# fz10_pow.net
KiCad netlist of a schematic drawn in EAGLE
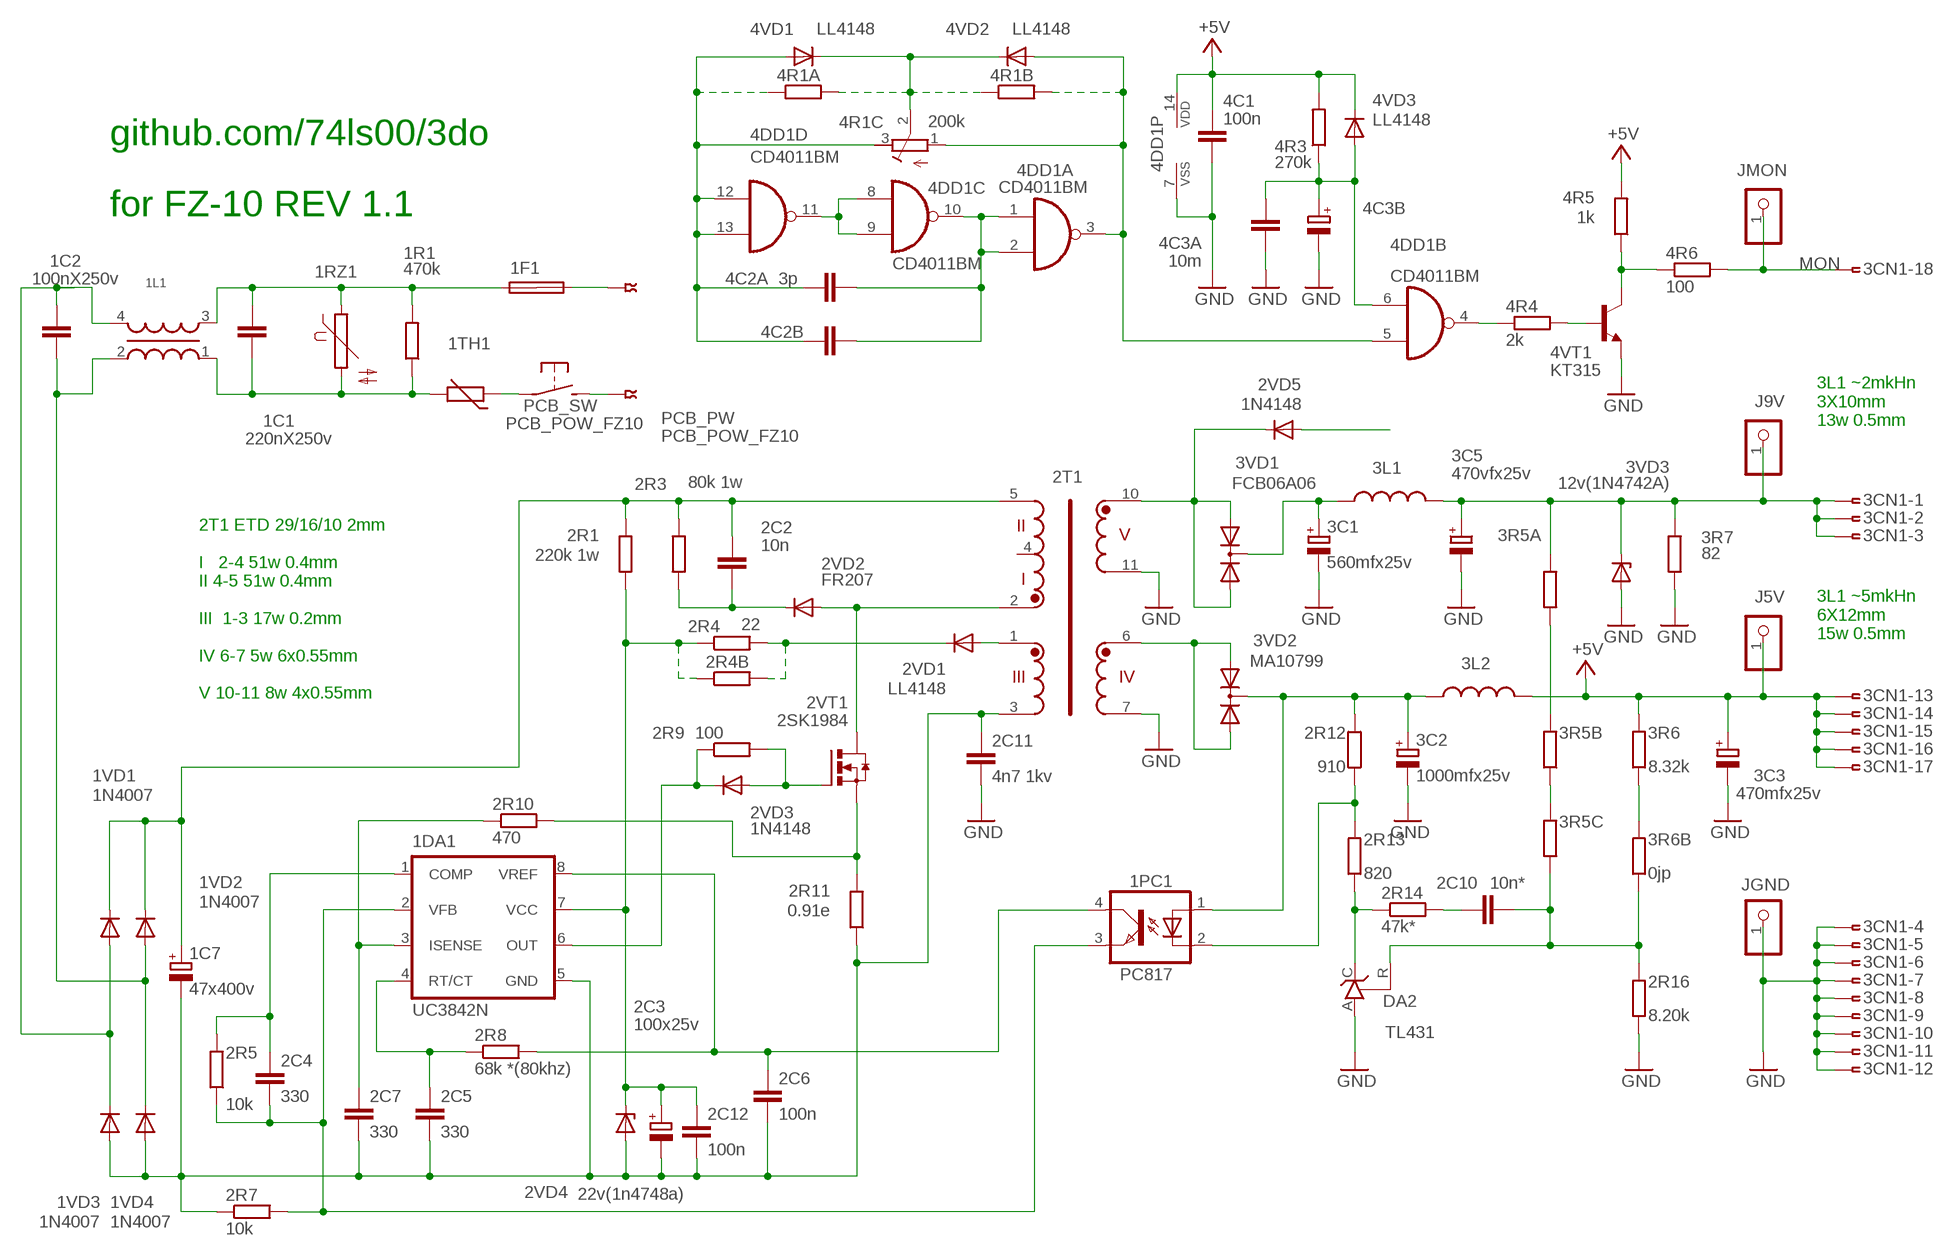
[diagram p0: schematic, sheet 1]

(export (version "E")
  (design (tool "Eeschema 10.0.6"))
  (components
    (comp (ref "1C1")
      (value "220nX250v")
      (footprint "eagle-import:C_26X9")
      (libsource (lib "eagle-import") (part "C26X9"))
    )
    (comp (ref "1C2")
      (value "100nX250v")
      (footprint "eagle-import:C150-084X183")
      (libsource (lib "eagle-import") (part "C-EU150-084X183"))
    )
    (comp (ref "1C7")
      (value "47x400v")
      (footprint "eagle-import:EB22,5D")
      (libsource (lib "eagle-import") (part "CPOL-EUE10-22.5"))
    )
    (comp (ref "1DA1")
      (value "UC3842N")
      (footprint "eagle-import:DIL08")
      (libsource (lib "eagle-import") (part "UC384N2"))
    )
    (comp (ref "1F1")
      (value "SHK20L")
      (footprint "eagle-import:SHK20L")
      (libsource (lib "eagle-import") (part "SHK20L"))
    )
    (comp (ref "1L1")
      (value "LFLF-10X13")
      (footprint "eagle-import:LF-10X13")
      (libsource (lib "eagle-import") (part "LFLF-10X13"))
    )
    (comp (ref "1PC1")
      (value "PC817")
      (footprint "eagle-import:DIL04")
      (fields (field (name "MPN") "PC817X4J000F"))
      (libsource (lib "eagle-import") (part "PC817"))
    )
    (comp (ref "1R1")
      (value "470k")
      (footprint "eagle-import:0309_12")
      (libsource (lib "eagle-import") (part "R-EU_0309/12"))
    )
    (comp (ref "1RZ1")
      (value "S1210")
      (footprint "eagle-import:S1210")
      (libsource (lib "eagle-import") (part "S1210"))
    )
    (comp (ref "1TH1")
      (value "THERMISTOR-7,5")
      (footprint "eagle-import:R-7,5")
      (libsource (lib "eagle-import") (part "THERMISTOR-7,5"))
    )
    (comp (ref "1VD1")
      (value "1N4007")
      (footprint "eagle-import:DO41-10")
      (libsource (lib "eagle-import") (part "1N4004"))
    )
    (comp (ref "1VD2")
      (value "1N4007")
      (footprint "eagle-import:DO41-10")
      (libsource (lib "eagle-import") (part "1N4004"))
    )
    (comp (ref "1VD3")
      (value "1N4007")
      (footprint "eagle-import:DO41-10")
      (libsource (lib "eagle-import") (part "1N4004"))
    )
    (comp (ref "1VD4")
      (value "1N4007")
      (footprint "eagle-import:DO41-10")
      (libsource (lib "eagle-import") (part "1N4004"))
    )
    (comp (ref "2C2")
      (value "10n")
      (footprint "eagle-import:C075-032X103")
      (libsource (lib "eagle-import") (part "C-EU075-032X103"))
    )
    (comp (ref "2C3")
      (value "100x25v")
      (footprint "eagle-import:E2,5-6")
      (libsource (lib "eagle-import") (part "CPOL-EUE2.5-6"))
    )
    (comp (ref "2C4")
      (value "330")
      (footprint "eagle-import:C050-025X075")
      (libsource (lib "eagle-import") (part "C-EU050-025X075"))
    )
    (comp (ref "2C5")
      (value "330")
      (footprint "eagle-import:C050-025X075")
      (libsource (lib "eagle-import") (part "C-EU050-025X075"))
    )
    (comp (ref "2C6")
      (value "100n")
      (footprint "eagle-import:C0805")
      (libsource (lib "eagle-import") (part "C-EUC0805"))
    )
    (comp (ref "2C7")
      (value "330")
      (footprint "eagle-import:C050-025X075")
      (libsource (lib "eagle-import") (part "C-EU050-025X075"))
    )
    (comp (ref "2C10")
      (value "10n*")
      (footprint "eagle-import:C050-025X075")
      (libsource (lib "eagle-import") (part "C-EU050-025X075"))
    )
    (comp (ref "2C11")
      (value "4n7 1kv")
      (footprint "eagle-import:C075-032X103")
      (libsource (lib "eagle-import") (part "C-EU075-032X103"))
    )
    (comp (ref "2C12")
      (value "100n")
      (footprint "eagle-import:C0805")
      (libsource (lib "eagle-import") (part "C-EUC0805"))
    )
    (comp (ref "2R1")
      (value "220k 1w")
      (footprint "eagle-import:P0613_15")
      (libsource (lib "eagle-import") (part "R-EU_0613/15"))
    )
    (comp (ref "2R3")
      (value "80k 1w")
      (footprint "eagle-import:P0613_15")
      (libsource (lib "eagle-import") (part "R-EU_0613/15"))
    )
    (comp (ref "2R4")
      (value "22")
      (footprint "eagle-import:M0805")
      (libsource (lib "eagle-import") (part "R-EU_M0805"))
    )
    (comp (ref "2R4B")
      (value "R-EU_0207/10")
      (footprint "eagle-import:0207_10")
      (libsource (lib "eagle-import") (part "R-EU_0207/10"))
    )
    (comp (ref "2R5")
      (value "10k")
      (footprint "eagle-import:M0805")
      (libsource (lib "eagle-import") (part "R-EU_M0805"))
    )
    (comp (ref "2R7")
      (value "10k")
      (footprint "eagle-import:R0805")
      (libsource (lib "eagle-import") (part "R-EU_R0805"))
    )
    (comp (ref "2R8")
      (value "68k *(80khz)")
      (footprint "eagle-import:R0805")
      (libsource (lib "eagle-import") (part "R-EU_R0805"))
    )
    (comp (ref "2R9")
      (value "100")
      (footprint "eagle-import:0204_7")
      (libsource (lib "eagle-import") (part "R-EU_0204/7"))
    )
    (comp (ref "2R10")
      (value "470")
      (footprint "eagle-import:0207_10")
      (libsource (lib "eagle-import") (part "R-EU_0207/10"))
    )
    (comp (ref "2R11")
      (value "0.91e")
      (footprint "eagle-import:P0613_15")
      (libsource (lib "eagle-import") (part "R-EU_0613/15"))
    )
    (comp (ref "2R12")
      (value "910")
      (footprint "eagle-import:R1206")
      (libsource (lib "eagle-import") (part "R-EU_R1206"))
    )
    (comp (ref "2R13")
      (value "820")
      (footprint "eagle-import:0207_10")
      (libsource (lib "eagle-import") (part "R-EU_0207/10"))
    )
    (comp (ref "2R14")
      (value "47k*")
      (footprint "eagle-import:R1206")
      (libsource (lib "eagle-import") (part "R-EU_R1206"))
    )
    (comp (ref "2R16")
      (value "8.20k")
      (footprint "eagle-import:R1206")
      (libsource (lib "eagle-import") (part "R-EU_R1206"))
    )
    (comp (ref "2T1")
      (value "TRANS_ER29")
      (footprint "eagle-import:ER29")
      (libsource (lib "eagle-import") (part "TRANS_ER29"))
    )
    (comp (ref "2VD1")
      (value "LL4148")
      (footprint "eagle-import:SOD80C")
      (libsource (lib "eagle-import") (part "DIODE-SOD80C"))
    )
    (comp (ref "2VD2")
      (value "FR207")
      (footprint "eagle-import:DO35-10")
      (libsource (lib "eagle-import") (part "1N4148DO35-10"))
    )
    (comp (ref "2VD3")
      (value "1N4148")
      (footprint "eagle-import:DO35-7")
      (libsource (lib "eagle-import") (part "1N4148DO35-7"))
    )
    (comp (ref "2VD4")
      (value "22v(1n4748a)")
      (footprint "eagle-import:DO35Z10")
      (libsource (lib "eagle-import") (part "ZENER-DIODEDO35Z10"))
    )
    (comp (ref "2VD5")
      (value "1N4148")
      (footprint "eagle-import:DO35-7")
      (libsource (lib "eagle-import") (part "1N4148DO35-7"))
    )
    (comp (ref "2VT1")
      (value "2SK1984")
      (footprint "eagle-import:TO262-V")
      (libsource (lib "eagle-import") (part "IRF3704L-V"))
    )
    (comp (ref "3C1")
      (value "560mfx25v")
      (footprint "eagle-import:E5-10,5")
      (libsource (lib "eagle-import") (part "CPOL-EUE5-10.5"))
    )
    (comp (ref "3C2")
      (value "1000mfx25v")
      (footprint "eagle-import:E5-13")
      (libsource (lib "eagle-import") (part "CPOL-EUE5-13"))
    )
    (comp (ref "3C3")
      (value "470mfx25v")
      (footprint "eagle-import:E5-8,5")
      (libsource (lib "eagle-import") (part "CPOL-EUE5-8.5"))
    )
    (comp (ref "3C5")
      (value "470vfx25v")
      (footprint "eagle-import:E5-8,5")
      (libsource (lib "eagle-import") (part "CPOL-EUE5-8.5"))
    )
    (comp (ref "3CN1")
      (value "FTOP-18")
      (footprint "eagle-import:FTOP-18")
      (libsource (lib "eagle-import") (part "FTOP-18"))
    )
    (comp (ref "3L1")
      (value "L-USTFI0305")
      (footprint "eagle-import:TFI0305")
      (libsource (lib "eagle-import") (part "L-USTFI0305"))
    )
    (comp (ref "3L2")
      (value "L-USTFI0305")
      (footprint "eagle-import:TFI0305")
      (libsource (lib "eagle-import") (part "L-USTFI0305"))
    )
    (comp (ref "3R5A")
      (value "R-EU_M1206")
      (footprint "eagle-import:M1206")
      (libsource (lib "eagle-import") (part "R-EU_M1206"))
    )
    (comp (ref "3R5B")
      (value "R-EU_M1206")
      (footprint "eagle-import:M1206")
      (libsource (lib "eagle-import") (part "R-EU_M1206"))
    )
    (comp (ref "3R5C")
      (value "R-EU_0207/10")
      (footprint "eagle-import:0207_10")
      (libsource (lib "eagle-import") (part "R-EU_0207/10"))
    )
    (comp (ref "3R6")
      (value "8.32k")
      (footprint "eagle-import:0204_7")
      (libsource (lib "eagle-import") (part "R-EU_0204/7"))
    )
    (comp (ref "3R6B")
      (value "0jp")
      (footprint "eagle-import:0204_7")
      (libsource (lib "eagle-import") (part "R-EU_0204/7"))
    )
    (comp (ref "3R7")
      (value "82")
      (footprint "eagle-import:P0613_15")
      (libsource (lib "eagle-import") (part "R-EU_0613/15"))
    )
    (comp (ref "3VD1")
      (value "FCB06A06")
      (footprint "eagle-import:TO220ABS")
      (libsource (lib "eagle-import") (part "BYV32"))
    )
    (comp (ref "3VD2")
      (value "MA10799")
      (footprint "eagle-import:TO220ABS")
      (libsource (lib "eagle-import") (part "BYV32"))
    )
    (comp (ref "3VD3")
      (value "12v(1N4742A)")
      (footprint "eagle-import:DO34Z7")
      (libsource (lib "eagle-import") (part "ZENER-DIODEDO34-7"))
    )
    (comp (ref "4C1")
      (value "100n")
      (footprint "eagle-import:C0805")
      (libsource (lib "eagle-import") (part "C-EUC0805"))
    )
    (comp (ref "4C2A")
      (value "3p")
      (footprint "eagle-import:C050-025X075")
      (libsource (lib "eagle-import") (part "C-EU050-025X075"))
    )
    (comp (ref "4C2B")
      (value "C-EUC1206")
      (footprint "eagle-import:C1206")
      (libsource (lib "eagle-import") (part "C-EUC1206"))
    )
    (comp (ref "4C3A")
      (value "10m")
      (footprint "eagle-import:C1812")
      (libsource (lib "eagle-import") (part "C-EUC1812"))
    )
    (comp (ref "4C3B")
      (value "CPOL-EUE2.5-5")
      (footprint "eagle-import:E2,5-5")
      (libsource (lib "eagle-import") (part "CPOL-EUE2.5-5"))
    )
    (comp (ref "4DD1")
      (value "CD4011BM")
      (footprint "eagle-import:SO14")
      (libsource (lib "eagle-import") (part "4011D"))
    )
    (comp (ref "4R1A")
      (value "R-EU_R1206")
      (footprint "eagle-import:R1206")
      (libsource (lib "eagle-import") (part "R-EU_R1206"))
    )
    (comp (ref "4R1B")
      (value "R-EU_R1206")
      (footprint "eagle-import:R1206")
      (libsource (lib "eagle-import") (part "R-EU_R1206"))
    )
    (comp (ref "4R1C")
      (value "200k")
      (footprint "eagle-import:RTRIM3296W")
      (libsource (lib "eagle-import") (part "R-TRIMM3296W"))
    )
    (comp (ref "4R3")
      (value "270k")
      (footprint "eagle-import:R1206")
      (libsource (lib "eagle-import") (part "R-EU_R1206"))
    )
    (comp (ref "4R4")
      (value "2k")
      (footprint "eagle-import:R1206")
      (libsource (lib "eagle-import") (part "R-EU_R1206"))
    )
    (comp (ref "4R5")
      (value "1k")
      (footprint "eagle-import:R1206")
      (libsource (lib "eagle-import") (part "R-EU_R1206"))
    )
    (comp (ref "4R6")
      (value "100")
      (footprint "eagle-import:R1206")
      (libsource (lib "eagle-import") (part "R-EU_R1206"))
    )
    (comp (ref "4VD1")
      (value "LL4148")
      (footprint "eagle-import:SOD80C")
      (libsource (lib "eagle-import") (part "DIODE-SOD80C"))
    )
    (comp (ref "4VD2")
      (value "LL4148")
      (footprint "eagle-import:SOD80C")
      (libsource (lib "eagle-import") (part "DIODE-SOD80C"))
    )
    (comp (ref "4VD3")
      (value "LL4148")
      (footprint "eagle-import:SOD80C")
      (libsource (lib "eagle-import") (part "DIODE-SOD80C"))
    )
    (comp (ref "4VT1")
      (value "KT315")
      (footprint "eagle-import:TO92-ECB")
      (libsource (lib "eagle-import") (part "-NPN-TO92-ECB"))
    )
    (comp (ref "DA2")
      (value "TL431")
      (footprint "eagle-import:TO92-CLP")
      (libsource (lib "eagle-import") (part "TL431CLP"))
    )
    (comp (ref "J5V")
      (value "PINHD-1X1")
      (footprint "eagle-import:1X01")
      (libsource (lib "eagle-import") (part "PINHD-1X1"))
    )
    (comp (ref "J9V")
      (value "PINHD-1X1")
      (footprint "eagle-import:1X01")
      (libsource (lib "eagle-import") (part "PINHD-1X1"))
    )
    (comp (ref "JGND")
      (value "PINHD-1X1")
      (footprint "eagle-import:1X01")
      (libsource (lib "eagle-import") (part "PINHD-1X1"))
    )
    (comp (ref "JMON")
      (value "PINHD-1X1")
      (footprint "eagle-import:1X01")
      (libsource (lib "eagle-import") (part "PINHD-1X1"))
    )
    (comp (ref "PCB")
      (value "PCB_POW_FZ10")
      (footprint "eagle-import:POW_FZ10")
      (libsource (lib "eagle-import") (part "PCB_POW_FZ10"))
    )
  )
  (nets
    (net (code "1") (name "+5V") (class "Default")
      (node (ref "3C3") (pin "+") (pinfunction "+_+") (pintype "passive"))
      (node (ref "3CN1") (pin "13") (pinfunction "1_13") (pintype "passive"))
      (node (ref "3CN1") (pin "14") (pinfunction "1_14") (pintype "passive"))
      (node (ref "3CN1") (pin "15") (pinfunction "1_15") (pintype "passive"))
      (node (ref "3CN1") (pin "16") (pinfunction "1_16") (pintype "passive"))
      (node (ref "3CN1") (pin "17") (pinfunction "1_17") (pintype "passive"))
      (node (ref "3L2") (pin "2") (pinfunction "2_2") (pintype "passive"))
      (node (ref "3R6") (pin "2") (pinfunction "2_2") (pintype "passive"))
      (node (ref "4C1") (pin "1") (pinfunction "1_1") (pintype "passive"))
      (node (ref "4DD1") (pin "14") (pinfunction "VDD_14") (pintype "power_in"))
      (node (ref "4R3") (pin "2") (pinfunction "2_2") (pintype "passive"))
      (node (ref "4R5") (pin "2") (pinfunction "2_2") (pintype "passive"))
      (node (ref "4VD3") (pin "C") (pinfunction "C_C") (pintype "passive"))
      (node (ref "J5V") (pin "1") (pinfunction "1_1") (pintype "passive"))
    )
    (net (code "2") (name "/MON") (class "Default")
      (node (ref "3CN1") (pin "18") (pinfunction "1_18") (pintype "passive"))
      (node (ref "4R6") (pin "2") (pinfunction "2_2") (pintype "passive"))
      (node (ref "JMON") (pin "1") (pinfunction "1_1") (pintype "passive"))
    )
    (net (code "3") (name "GND") (class "Default")
      (node (ref "2C11") (pin "2") (pinfunction "2_2") (pintype "passive"))
      (node (ref "2R16") (pin "1") (pinfunction "1_1") (pintype "passive"))
      (node (ref "2T1") (pin "11") (pinfunction "9V2_11") (pintype "bidirectional"))
      (node (ref "2T1") (pin "7") (pinfunction "O2.2_7") (pintype "bidirectional"))
      (node (ref "3C1") (pin "-") (pinfunction "-_-") (pintype "passive"))
      (node (ref "3C2") (pin "-") (pinfunction "-_-") (pintype "passive"))
      (node (ref "3C3") (pin "-") (pinfunction "-_-") (pintype "passive"))
      (node (ref "3C5") (pin "-") (pinfunction "-_-") (pintype "passive"))
      (node (ref "3CN1") (pin "10") (pinfunction "1_10") (pintype "passive"))
      (node (ref "3CN1") (pin "11") (pinfunction "1_11") (pintype "passive"))
      (node (ref "3CN1") (pin "12") (pinfunction "1_12") (pintype "passive"))
      (node (ref "3CN1") (pin "4") (pinfunction "1_4") (pintype "passive"))
      (node (ref "3CN1") (pin "5") (pinfunction "1_5") (pintype "passive"))
      (node (ref "3CN1") (pin "6") (pinfunction "1_6") (pintype "passive"))
      (node (ref "3CN1") (pin "7") (pinfunction "1_7") (pintype "passive"))
      (node (ref "3CN1") (pin "8") (pinfunction "1_8") (pintype "passive"))
      (node (ref "3CN1") (pin "9") (pinfunction "1_9") (pintype "passive"))
      (node (ref "3R7") (pin "1") (pinfunction "1_1") (pintype "passive"))
      (node (ref "3VD3") (pin "A") (pinfunction "A_A") (pintype "passive"))
      (node (ref "4C1") (pin "2") (pinfunction "2_2") (pintype "passive"))
      (node (ref "4C3A") (pin "2") (pinfunction "2_2") (pintype "passive"))
      (node (ref "4C3B") (pin "-") (pinfunction "-_-") (pintype "passive"))
      (node (ref "4DD1") (pin "7") (pinfunction "VSS_7") (pintype "power_in"))
      (node (ref "4VT1") (pin "E") (pinfunction "E_E") (pintype "passive"))
      (node (ref "DA2") (pin "A") (pinfunction "A_A") (pintype "passive"))
      (node (ref "JGND") (pin "1") (pinfunction "1_1") (pintype "passive"))
    )
    (net (code "4") (name "Net-(1C1-Pad1)") (class "Default")
      (node (ref "1C1") (pin "1") (pinfunction "1_1") (pintype "passive"))
      (node (ref "1F1") (pin "2A") (pinfunction "2A_2A") (pintype "passive"))
      (node (ref "1L1") (pin "3") (pinfunction "3_3") (pintype "bidirectional"))
      (node (ref "1R1") (pin "2") (pinfunction "2_2") (pintype "passive"))
      (node (ref "1RZ1") (pin "1") (pinfunction "1_1") (pintype "passive"))
    )
    (net (code "5") (name "Net-(1C1-Pad2)") (class "Default")
      (node (ref "1C1") (pin "2") (pinfunction "2_2") (pintype "passive"))
      (node (ref "1L1") (pin "1") (pinfunction "1_1") (pintype "bidirectional"))
      (node (ref "1R1") (pin "1") (pinfunction "1_1") (pintype "passive"))
      (node (ref "1RZ1") (pin "2") (pinfunction "2_2") (pintype "passive"))
      (node (ref "1TH1") (pin "2") (pinfunction "2_2") (pintype "passive"))
    )
    (net (code "6") (name "Net-(1C2-Pad1)") (class "Default")
      (node (ref "1C2") (pin "1") (pinfunction "1_1") (pintype "passive"))
      (node (ref "1L1") (pin "4") (pinfunction "4_4") (pintype "bidirectional"))
      (node (ref "1VD1") (pin "A") (pinfunction "A_A") (pintype "passive"))
      (node (ref "1VD3") (pin "C") (pinfunction "C_C") (pintype "passive"))
    )
    (net (code "7") (name "Net-(1C2-Pad2)") (class "Default")
      (node (ref "1C2") (pin "2") (pinfunction "2_2") (pintype "passive"))
      (node (ref "1L1") (pin "2") (pinfunction "2_2") (pintype "bidirectional"))
      (node (ref "1VD2") (pin "A") (pinfunction "A_A") (pintype "passive"))
      (node (ref "1VD4") (pin "C") (pinfunction "C_C") (pintype "passive"))
    )
    (net (code "8") (name "Net-(1DA1-COMP)") (class "Default")
      (node (ref "1DA1") (pin "1") (pinfunction "COMP_1") (pintype "passive"))
      (node (ref "2C4") (pin "1") (pinfunction "1_1") (pintype "passive"))
      (node (ref "2R5") (pin "2") (pinfunction "2_2") (pintype "passive"))
    )
    (net (code "9") (name "Net-(1DA1-GND)") (class "Default")
      (node (ref "1C7") (pin "-") (pinfunction "-_-") (pintype "passive"))
      (node (ref "1DA1") (pin "5") (pinfunction "GND_5") (pintype "power_in"))
      (node (ref "1VD3") (pin "A") (pinfunction "A_A") (pintype "passive"))
      (node (ref "1VD4") (pin "A") (pinfunction "A_A") (pintype "passive"))
      (node (ref "2C11") (pin "1") (pinfunction "1_1") (pintype "passive"))
      (node (ref "2C12") (pin "2") (pinfunction "2_2") (pintype "passive"))
      (node (ref "2C3") (pin "-") (pinfunction "-_-") (pintype "passive"))
      (node (ref "2C5") (pin "2") (pinfunction "2_2") (pintype "passive"))
      (node (ref "2C6") (pin "2") (pinfunction "2_2") (pintype "passive"))
      (node (ref "2C7") (pin "2") (pinfunction "2_2") (pintype "passive"))
      (node (ref "2R11") (pin "1") (pinfunction "1_1") (pintype "passive"))
      (node (ref "2R7") (pin "1") (pinfunction "1_1") (pintype "passive"))
      (node (ref "2T1") (pin "3") (pinfunction "OP2_3") (pintype "bidirectional"))
      (node (ref "2VD4") (pin "A") (pinfunction "A_A") (pintype "passive"))
    )
    (net (code "10") (name "Net-(1DA1-ISENSE)") (class "Default")
      (node (ref "1DA1") (pin "3") (pinfunction "ISENSE_3") (pintype "input"))
      (node (ref "2C7") (pin "1") (pinfunction "1_1") (pintype "passive"))
      (node (ref "2R10") (pin "1") (pinfunction "1_1") (pintype "passive"))
    )
    (net (code "11") (name "Net-(1DA1-OUT)") (class "Default")
      (node (ref "1DA1") (pin "6") (pinfunction "OUT_6") (pintype "output"))
      (node (ref "2R9") (pin "1") (pinfunction "1_1") (pintype "passive"))
      (node (ref "2VD3") (pin "C") (pinfunction "C_C") (pintype "passive"))
    )
    (net (code "12") (name "Net-(1DA1-RT{slash}CT)") (class "Default")
      (node (ref "1DA1") (pin "4") (pinfunction "RT/CT_4") (pintype "passive"))
      (node (ref "2C5") (pin "1") (pinfunction "1_1") (pintype "passive"))
      (node (ref "2R8") (pin "1") (pinfunction "1_1") (pintype "passive"))
    )
    (net (code "13") (name "Net-(1DA1-VCC)") (class "Default")
      (node (ref "1DA1") (pin "7") (pinfunction "VCC_7") (pintype "power_in"))
      (node (ref "2C12") (pin "1") (pinfunction "1_1") (pintype "passive"))
      (node (ref "2C3") (pin "+") (pinfunction "+_+") (pintype "passive"))
      (node (ref "2R1") (pin "1") (pinfunction "1_1") (pintype "passive"))
      (node (ref "2R4") (pin "1") (pinfunction "1_1") (pintype "passive"))
      (node (ref "2R4B") (pin "1") (pinfunction "1_1") (pintype "passive"))
      (node (ref "2VD4") (pin "C") (pinfunction "C_C") (pintype "passive"))
    )
    (net (code "14") (name "Net-(1DA1-VFB)") (class "Default")
      (node (ref "1DA1") (pin "2") (pinfunction "VFB_2") (pintype "input"))
      (node (ref "1PC1") (pin "3") (pinfunction "EMIT_3") (pintype "passive"))
      (node (ref "2C4") (pin "2") (pinfunction "2_2") (pintype "passive"))
      (node (ref "2R5") (pin "1") (pinfunction "1_1") (pintype "passive"))
      (node (ref "2R7") (pin "2") (pinfunction "2_2") (pintype "passive"))
    )
    (net (code "15") (name "Net-(1DA1-VREF)") (class "Default")
      (node (ref "1DA1") (pin "8") (pinfunction "VREF_8") (pintype "passive"))
      (node (ref "1PC1") (pin "4") (pinfunction "COL_4") (pintype "passive"))
      (node (ref "2C6") (pin "1") (pinfunction "1_1") (pintype "passive"))
      (node (ref "2R8") (pin "2") (pinfunction "2_2") (pintype "passive"))
    )
    (net (code "16") (name "Net-(1PC1-A)") (class "Default")
      (node (ref "1PC1") (pin "1") (pinfunction "A_1") (pintype "passive"))
      (node (ref "2R12") (pin "2") (pinfunction "2_2") (pintype "passive"))
      (node (ref "3C2") (pin "+") (pinfunction "+_+") (pintype "passive"))
      (node (ref "3L2") (pin "1") (pinfunction "1_1") (pintype "passive"))
      (node (ref "3VD2") (pin "C") (pinfunction "C_C") (pintype "passive"))
    )
    (net (code "17") (name "Net-(1PC1-C)") (class "Default")
      (node (ref "1PC1") (pin "2") (pinfunction "C_2") (pintype "passive"))
      (node (ref "2R12") (pin "1") (pinfunction "1_1") (pintype "passive"))
      (node (ref "2R13") (pin "2") (pinfunction "2_2") (pintype "passive"))
    )
    (net (code "18") (name "Net-(2C2-Pad2)") (class "Default")
      (node (ref "2C2") (pin "2") (pinfunction "2_2") (pintype "passive"))
      (node (ref "2R3") (pin "1") (pinfunction "1_1") (pintype "passive"))
      (node (ref "2VD2") (pin "C") (pinfunction "C_C") (pintype "passive"))
    )
    (net (code "19") (name "Net-(2C10-Pad1)") (class "Default")
      (node (ref "2C10") (pin "1") (pinfunction "1_1") (pintype "passive"))
      (node (ref "2R16") (pin "2") (pinfunction "2_2") (pintype "passive"))
      (node (ref "3R5C") (pin "1") (pinfunction "1_1") (pintype "passive"))
      (node (ref "3R6B") (pin "1") (pinfunction "1_1") (pintype "passive"))
      (node (ref "DA2") (pin "R") (pinfunction "R_R") (pintype "passive"))
    )
    (net (code "20") (name "Net-(2C10-Pad2)") (class "Default")
      (node (ref "2C10") (pin "2") (pinfunction "2_2") (pintype "passive"))
      (node (ref "2R14") (pin "2") (pinfunction "2_2") (pintype "passive"))
    )
    (net (code "21") (name "Net-(2R4-Pad2)") (class "Default")
      (node (ref "2R4") (pin "2") (pinfunction "2_2") (pintype "passive"))
      (node (ref "2R4B") (pin "2") (pinfunction "2_2") (pintype "passive"))
      (node (ref "2VD1") (pin "C") (pinfunction "C_C") (pintype "passive"))
    )
    (net (code "22") (name "Net-(2R13-Pad1)") (class "Default")
      (node (ref "2R13") (pin "1") (pinfunction "1_1") (pintype "passive"))
      (node (ref "2R14") (pin "1") (pinfunction "1_1") (pintype "passive"))
      (node (ref "DA2") (pin "C") (pinfunction "C_C") (pintype "passive"))
    )
    (net (code "23") (name "Net-(2T1-9V1)") (class "Default")
      (node (ref "2T1") (pin "10") (pinfunction "9V1_10") (pintype "bidirectional"))
      (node (ref "2VD5") (pin "C") (pinfunction "C_C") (pintype "passive"))
      (node (ref "3VD1") (pin "A1") (pinfunction "A1_A1") (pintype "passive"))
      (node (ref "3VD1") (pin "A2") (pinfunction "A2_A2") (pintype "passive"))
    )
    (net (code "24") (name "Net-(2T1-IN1)") (class "Default")
      (node (ref "1C7") (pin "+") (pinfunction "+_+") (pintype "passive"))
      (node (ref "1VD1") (pin "C") (pinfunction "C_C") (pintype "passive"))
      (node (ref "1VD2") (pin "C") (pinfunction "C_C") (pintype "passive"))
      (node (ref "2C2") (pin "1") (pinfunction "1_1") (pintype "passive"))
      (node (ref "2R1") (pin "2") (pinfunction "2_2") (pintype "passive"))
      (node (ref "2R3") (pin "2") (pinfunction "2_2") (pintype "passive"))
      (node (ref "2T1") (pin "5") (pinfunction "IN1_5") (pintype "bidirectional"))
    )
    (net (code "25") (name "Net-(2T1-IN2)") (class "Default")
      (node (ref "2T1") (pin "2") (pinfunction "IN2_2") (pintype "bidirectional"))
      (node (ref "2VD2") (pin "A") (pinfunction "A_A") (pintype "passive"))
      (node (ref "2VT1") (pin "2") (pinfunction "D_2") (pintype "passive"))
    )
    (net (code "26") (name "Net-(2T1-O2.1)") (class "Default")
      (node (ref "2T1") (pin "6") (pinfunction "O2.1_6") (pintype "bidirectional"))
      (node (ref "3VD2") (pin "A1") (pinfunction "A1_A1") (pintype "passive"))
      (node (ref "3VD2") (pin "A2") (pinfunction "A2_A2") (pintype "passive"))
    )
    (net (code "27") (name "Net-(2T1-OP1)") (class "Default")
      (node (ref "2T1") (pin "1") (pinfunction "OP1_1") (pintype "bidirectional"))
      (node (ref "2VD1") (pin "A") (pinfunction "A_A") (pintype "passive"))
    )
    (net (code "28") (name "Net-(2VT1-G)") (class "Default")
      (node (ref "2R9") (pin "2") (pinfunction "2_2") (pintype "passive"))
      (node (ref "2VD3") (pin "A") (pinfunction "A_A") (pintype "passive"))
      (node (ref "2VT1") (pin "1") (pinfunction "G_1") (pintype "passive"))
    )
    (net (code "29") (name "Net-(2VT1-S)") (class "Default")
      (node (ref "2R10") (pin "2") (pinfunction "2_2") (pintype "passive"))
      (node (ref "2R11") (pin "2") (pinfunction "2_2") (pintype "passive"))
      (node (ref "2VT1") (pin "3") (pinfunction "S_3") (pintype "passive"))
    )
    (net (code "30") (name "Net-(3C1-Pad+)") (class "Default")
      (node (ref "3C1") (pin "+") (pinfunction "+_+") (pintype "passive"))
      (node (ref "3L1") (pin "1") (pinfunction "1_1") (pintype "passive"))
      (node (ref "3VD1") (pin "C") (pinfunction "C_C") (pintype "passive"))
    )
    (net (code "31") (name "Net-(3CN1K-1)") (class "Default")
      (node (ref "3C5") (pin "+") (pinfunction "+_+") (pintype "passive"))
      (node (ref "3CN1") (pin "1") (pinfunction "1_1") (pintype "passive"))
      (node (ref "3CN1") (pin "2") (pinfunction "1_2") (pintype "passive"))
      (node (ref "3CN1") (pin "3") (pinfunction "1_3") (pintype "passive"))
      (node (ref "3L1") (pin "2") (pinfunction "2_2") (pintype "passive"))
      (node (ref "3R5A") (pin "2") (pinfunction "2_2") (pintype "passive"))
      (node (ref "3R7") (pin "2") (pinfunction "2_2") (pintype "passive"))
      (node (ref "3VD3") (pin "C") (pinfunction "C_C") (pintype "passive"))
      (node (ref "J9V") (pin "1") (pinfunction "1_1") (pintype "passive"))
    )
    (net (code "32") (name "Net-(3R5A-Pad1)") (class "Default")
      (node (ref "3R5A") (pin "1") (pinfunction "1_1") (pintype "passive"))
      (node (ref "3R5B") (pin "2") (pinfunction "2_2") (pintype "passive"))
    )
    (net (code "33") (name "Net-(3R5B-Pad1)") (class "Default")
      (node (ref "3R5B") (pin "1") (pinfunction "1_1") (pintype "passive"))
      (node (ref "3R5C") (pin "2") (pinfunction "2_2") (pintype "passive"))
    )
    (net (code "34") (name "Net-(3R6-Pad1)") (class "Default")
      (node (ref "3R6") (pin "1") (pinfunction "1_1") (pintype "passive"))
      (node (ref "3R6B") (pin "2") (pinfunction "2_2") (pintype "passive"))
    )
    (net (code "35") (name "Net-(4DD1A-I0)") (class "Default")
      (node (ref "4C2A") (pin "1") (pinfunction "1_1") (pintype "passive"))
      (node (ref "4C2B") (pin "1") (pinfunction "1_1") (pintype "passive"))
      (node (ref "4DD1") (pin "1") (pinfunction "I0_1") (pintype "input"))
      (node (ref "4DD1") (pin "10") (pinfunction "O_10") (pintype "output"))
      (node (ref "4DD1") (pin "2") (pinfunction "I1_2") (pintype "input"))
    )
    (net (code "36") (name "Net-(4DD1A-O)") (class "Default")
      (node (ref "4DD1") (pin "3") (pinfunction "O_3") (pintype "output"))
      (node (ref "4DD1") (pin "5") (pinfunction "I0_5") (pintype "input"))
      (node (ref "4R1B") (pin "2") (pinfunction "2_2") (pintype "passive"))
      (node (ref "4R1C") (pin "1") (pinfunction "A_1") (pintype "passive"))
      (node (ref "4VD2") (pin "A") (pinfunction "A_A") (pintype "passive"))
    )
    (net (code "37") (name "Net-(4DD1B-I1)") (class "Default")
      (node (ref "4C3A") (pin "1") (pinfunction "1_1") (pintype "passive"))
      (node (ref "4C3B") (pin "+") (pinfunction "+_+") (pintype "passive"))
      (node (ref "4DD1") (pin "6") (pinfunction "I1_6") (pintype "input"))
      (node (ref "4R3") (pin "1") (pinfunction "1_1") (pintype "passive"))
      (node (ref "4VD3") (pin "A") (pinfunction "A_A") (pintype "passive"))
    )
    (net (code "38") (name "Net-(4DD1B-O)") (class "Default")
      (node (ref "4DD1") (pin "4") (pinfunction "O_4") (pintype "output"))
      (node (ref "4R4") (pin "1") (pinfunction "1_1") (pintype "passive"))
    )
    (net (code "39") (name "Net-(4DD1C-I0)") (class "Default")
      (node (ref "4DD1") (pin "11") (pinfunction "O_11") (pintype "output"))
      (node (ref "4DD1") (pin "8") (pinfunction "I0_8") (pintype "input"))
      (node (ref "4DD1") (pin "9") (pinfunction "I1_9") (pintype "input"))
    )
    (net (code "40") (name "Net-(4DD1D-I0)") (class "Default")
      (node (ref "4C2A") (pin "2") (pinfunction "2_2") (pintype "passive"))
      (node (ref "4C2B") (pin "2") (pinfunction "2_2") (pintype "passive"))
      (node (ref "4DD1") (pin "12") (pinfunction "I0_12") (pintype "input"))
      (node (ref "4DD1") (pin "13") (pinfunction "I1_13") (pintype "input"))
      (node (ref "4R1A") (pin "1") (pinfunction "1_1") (pintype "passive"))
      (node (ref "4R1C") (pin "3") (pinfunction "E_3") (pintype "passive"))
      (node (ref "4VD1") (pin "A") (pinfunction "A_A") (pintype "passive"))
    )
    (net (code "41") (name "Net-(4R1C-S)") (class "Default")
      (node (ref "4R1A") (pin "2") (pinfunction "2_2") (pintype "passive"))
      (node (ref "4R1B") (pin "1") (pinfunction "1_1") (pintype "passive"))
      (node (ref "4R1C") (pin "2") (pinfunction "S_2") (pintype "passive"))
      (node (ref "4VD1") (pin "C") (pinfunction "C_C") (pintype "passive"))
      (node (ref "4VD2") (pin "C") (pinfunction "C_C") (pintype "passive"))
    )
    (net (code "42") (name "Net-(4R4-Pad2)") (class "Default")
      (node (ref "4R4") (pin "2") (pinfunction "2_2") (pintype "passive"))
      (node (ref "4VT1") (pin "B") (pinfunction "B_B") (pintype "passive"))
    )
    (net (code "43") (name "Net-(4R5-Pad1)") (class "Default")
      (node (ref "4R5") (pin "1") (pinfunction "1_1") (pintype "passive"))
      (node (ref "4R6") (pin "1") (pinfunction "1_1") (pintype "passive"))
      (node (ref "4VT1") (pin "C") (pinfunction "C_C") (pintype "passive"))
    )
    (net (code "44") (name "Net-(PCBA-1)") (class "Default")
      (node (ref "PCB") (pin "POW1") (pinfunction "1_POW1") (pintype "passive"))
      (node (ref "PCB") (pin "SW2") (pinfunction "S_SW2") (pintype "passive"))
    )
    (net (code "45") (name "Net-(PCBA-2)") (class "Default")
      (node (ref "1F1") (pin "1A") (pinfunction "1A_1A") (pintype "passive"))
      (node (ref "PCB") (pin "POW2") (pinfunction "2_POW2") (pintype "passive"))
    )
    (net (code "46") (name "Net-(PCBB-P)") (class "Default")
      (node (ref "1TH1") (pin "1") (pinfunction "1_1") (pintype "passive"))
      (node (ref "PCB") (pin "SW1") (pinfunction "P_SW1") (pintype "passive"))
    )
    (net (code "47") (name "unconnected-(1F1-Pad1B)") (class "Default")
      (node (ref "1F1") (pin "1B") (pinfunction "1B_1B") (pintype "passive"))
    )
    (net (code "48") (name "unconnected-(1F1-Pad2B)") (class "Default")
      (node (ref "1F1") (pin "2B") (pinfunction "2B_2B") (pintype "passive"))
    )
    (net (code "49") (name "unconnected-(2T1-INC-Pad4)") (class "Default")
      (node (ref "2T1") (pin "4") (pinfunction "INC_4") (pintype "bidirectional"))
    )
    (net (code "50") (name "unconnected-(2VD5-PadA)") (class "Default")
      (node (ref "2VD5") (pin "A") (pinfunction "A_A") (pintype "passive"))
    )
  )
)
